# SynchDemod.net
KiCad netlist of a schematic drawn in Altium Designer
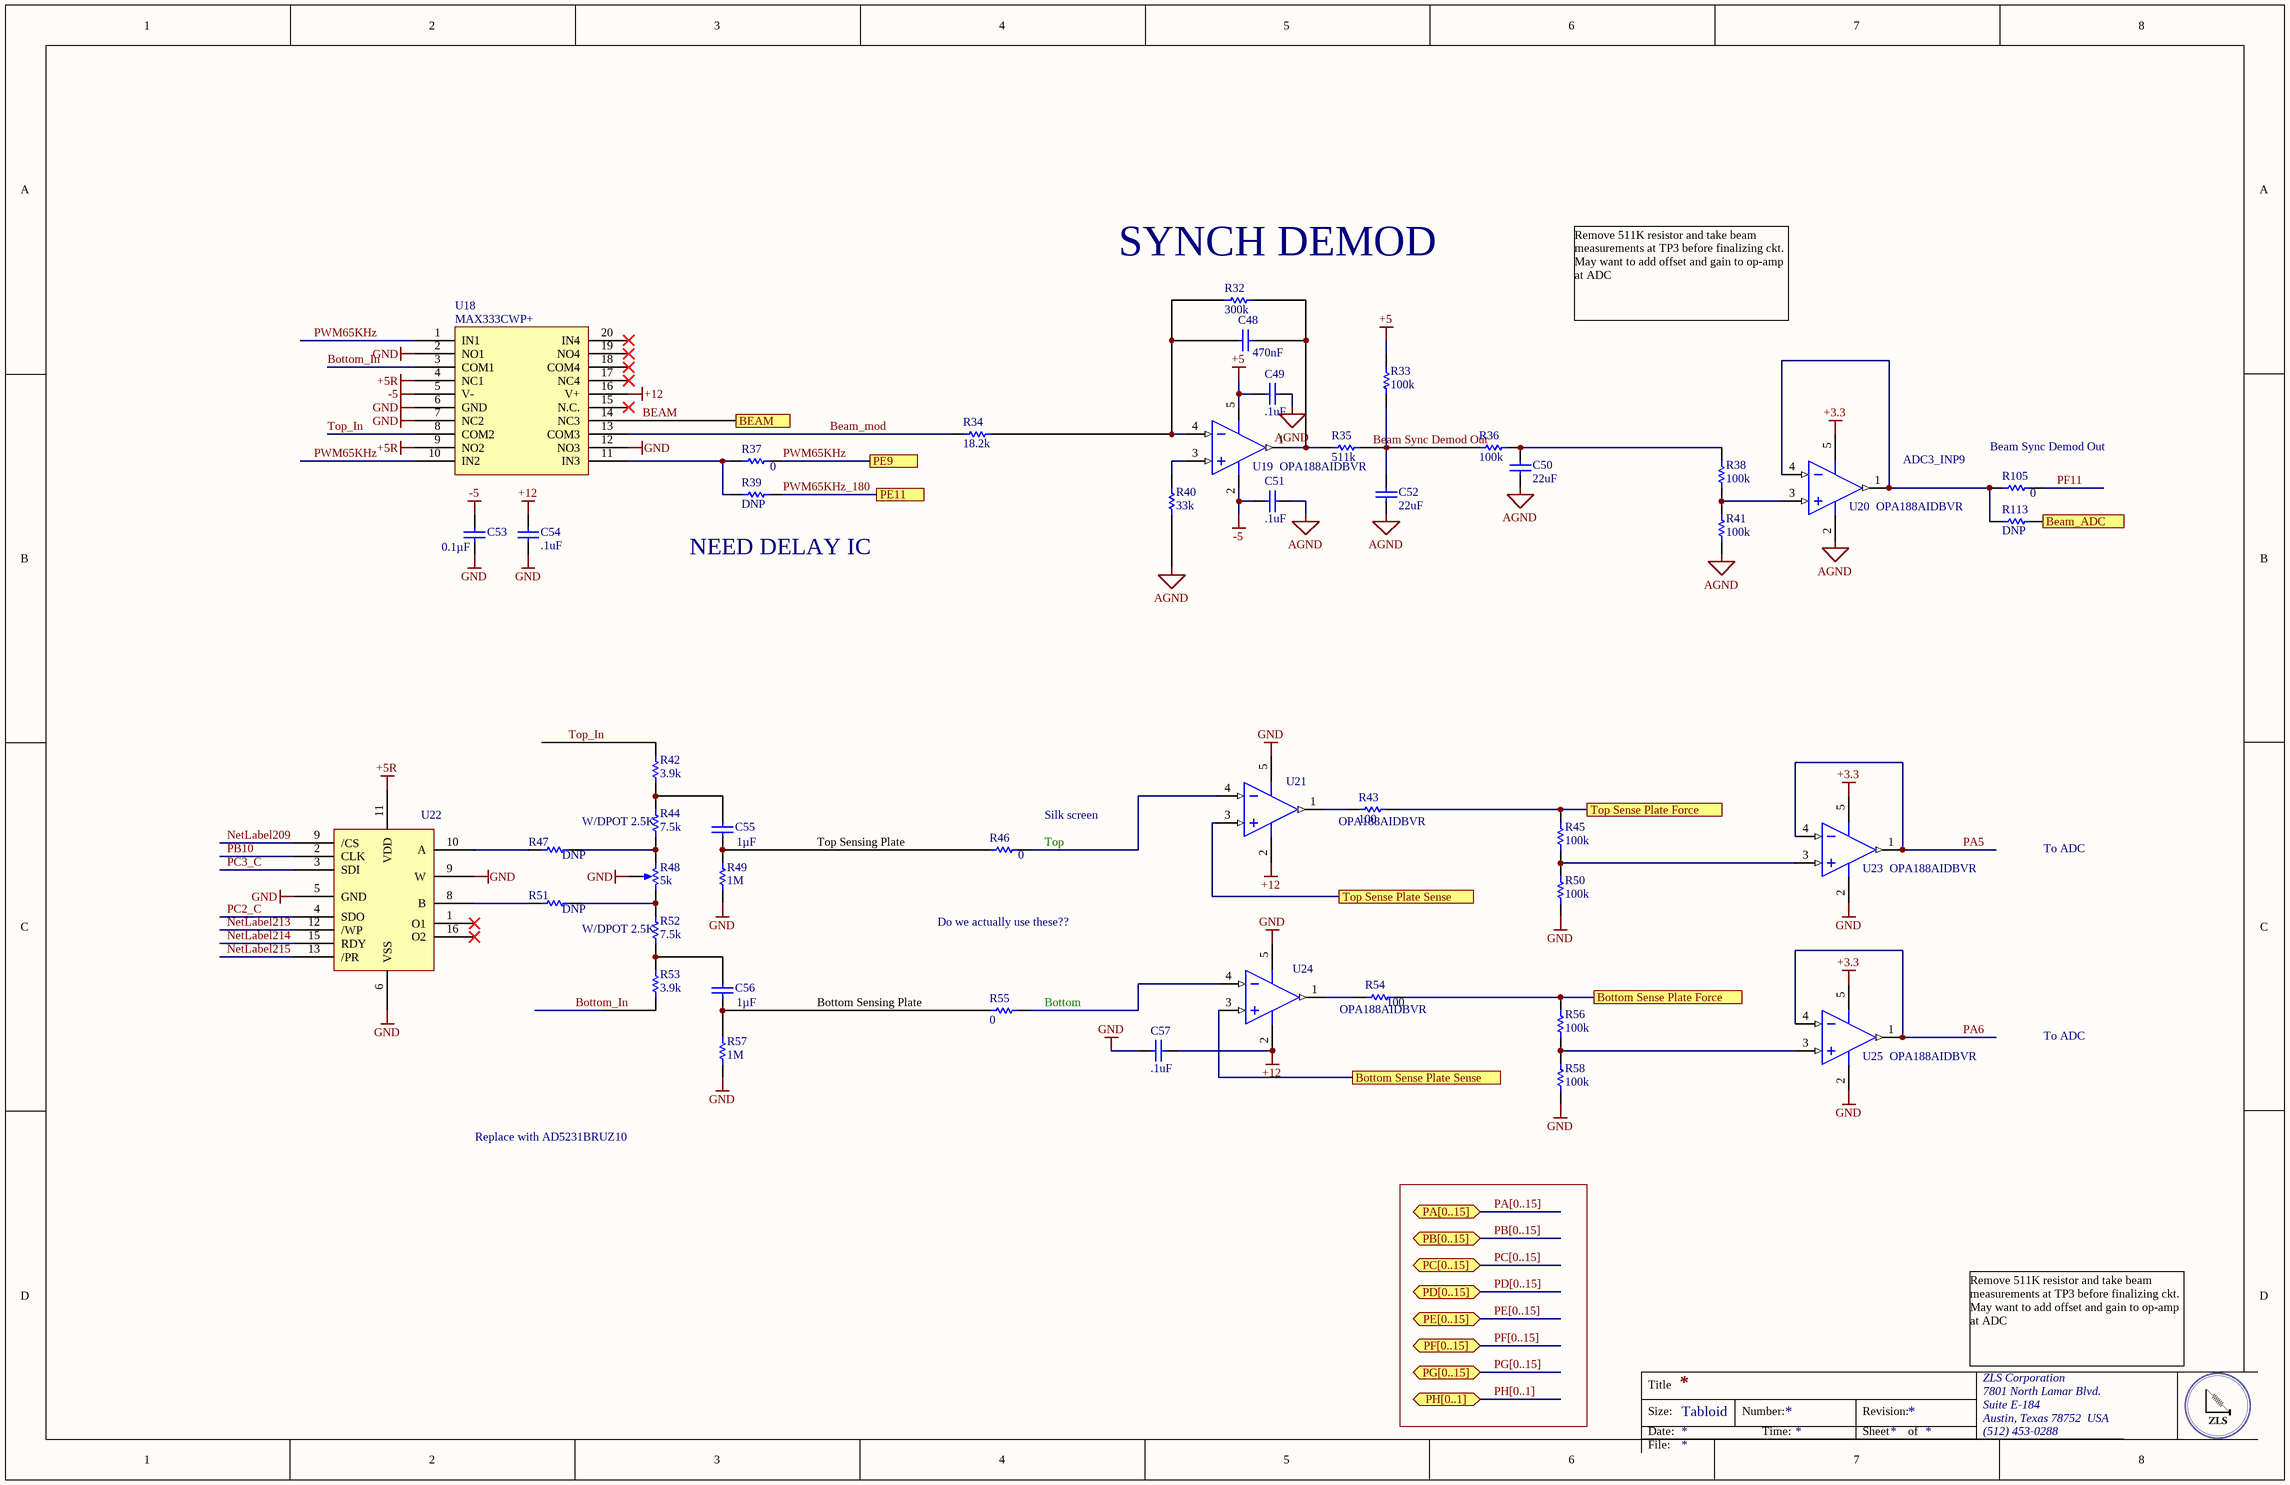
[diagram p0: SynchDemod.SchDoc]

(export (version "E")
  (design (tool "Eeschema 10.0.6"))
  (components
    (comp (ref "C48")
      (value "470nF")
      (footprint "CAPC0805(2012)75_L")
      (description "CAP 150pF 16V ±10% 0805 (2012 Metric) Thickness 0.75mm SMD")
      (fields (field (name "TOLERANCE") "Â±10%"))
      (libsource (lib "Altium Content Vault") (part "CMP-1036-02117-1"))
    )
    (comp (ref "C49")
      (value ".1uF")
      (footprint "CAPC0805(2012)75_L")
      (description "CAP 150pF 16V ±10% 0805 (2012 Metric) Thickness 0.75mm SMD")
      (fields (field (name "TOLERANCE") "Â±10%"))
      (libsource (lib "Altium Content Vault") (part "CMP-1036-02117-1"))
    )
    (comp (ref "C50")
      (value "22uF")
      (footprint "CAPC0805(2012)75_L")
      (description "CAP 150pF 16V ±10% 0805 (2012 Metric) Thickness 0.75mm SMD")
      (fields (field (name "TOLERANCE") "Â±10%"))
      (libsource (lib "Altium Content Vault") (part "CMP-1036-02117-1"))
    )
    (comp (ref "C51")
      (value ".1uF")
      (footprint "CAPC0805(2012)75_L")
      (description "CAP 150pF 16V ±10% 0805 (2012 Metric) Thickness 0.75mm SMD")
      (fields (field (name "TOLERANCE") "Â±10%"))
      (libsource (lib "Altium Content Vault") (part "CMP-1036-02117-1"))
    )
    (comp (ref "C52")
      (value "22uF")
      (footprint "CAPC0805(2012)75_L")
      (description "CAP 150pF 16V ±10% 0805 (2012 Metric) Thickness 0.75mm SMD")
      (fields (field (name "TOLERANCE") "Â±10%"))
      (libsource (lib "Altium Content Vault") (part "CMP-1036-02117-1"))
    )
    (comp (ref "C53")
      (value "CAP CER 0.1UF 25V X7R 0805")
      (footprint "CAPC0805(2012)145_N")
      (fields
        (field (name "MANUFACTURER") "Murata Electronics North America")
        (field (name "MANUFACTURER PART NUMBER") "GRM21BR71E104KA01L")
        (field (name "CAPACITANCE") "0.1µF")
        (field (name "TOLERANCE") "±10%")
      )
      (libsource (lib "Altium Content Vault") (part "CMP-1036-04795-1"))
    )
    (comp (ref "C54")
      (value ".1uF")
      (footprint "CAPC0805(2012)75_L")
      (description "CAP 150pF 16V ±10% 0805 (2012 Metric) Thickness 0.75mm SMD")
      (fields (field (name "TOLERANCE") "Â±10%"))
      (libsource (lib "Altium Content Vault") (part "CMP-1036-02117-1"))
    )
    (comp (ref "C55")
      (value "CAP CER 1UF 25V X7R 0805")
      (footprint "CAPC0805(2012)155_L")
      (fields
        (field (name "MANUFACTURER") "Murata Electronics North America")
        (field (name "MANUFACTURER PART NUMBER") "GRM21BR71E105KA99L")
        (field (name "CAPACITANCE") "1µF")
        (field (name "TOLERANCE") "±10%")
      )
      (libsource (lib "Altium Content Vault") (part "CMP-1036-04882-1"))
    )
    (comp (ref "C56")
      (value "CAP CER 1UF 25V X7R 0805")
      (footprint "CAPC0805(2012)155_L")
      (fields
        (field (name "MANUFACTURER") "Murata Electronics North America")
        (field (name "MANUFACTURER PART NUMBER") "GRM21BR71E105KA99L")
        (field (name "CAPACITANCE") "1µF")
        (field (name "TOLERANCE") "±10%")
      )
      (libsource (lib "Altium Content Vault") (part "CMP-1036-04882-1"))
    )
    (comp (ref "C57")
      (value ".1uF")
      (footprint "CAPC0805(2012)75_M")
      (description "CAP 33pF 25V ±2% 0805 (2012 Metric) Thickness 0.75mm SMD")
      (fields (field (name "TOLERANCE") "Â±2%"))
      (libsource (lib "Altium Content Vault") (part "CMP-1036-01414-1"))
    )
    (comp (ref "R32")
      (value "300k")
      (footprint "RESC0805(2012)_L")
      (description "2R55 0.125W 1% 0805 (2012 Metric)  SMD")
      (fields (field (name "TOLERANCE") "1 %") (field (name "POWER") "0.125 W"))
      (libsource (lib "Altium Content Vault") (part "CMP-1013-00215-1"))
    )
    (comp (ref "R33")
      (value "100k")
      (footprint "RESC0805(2012)_L")
      (description "2R55 0.125W 1% 0805 (2012 Metric)  SMD")
      (fields (field (name "TOLERANCE") "1 %") (field (name "POWER") "0.125 W"))
      (libsource (lib "Altium Content Vault") (part "CMP-1013-00215-1"))
    )
    (comp (ref "R34")
      (value "18.2k")
      (footprint "RESC0805(2012)_L")
      (description "2R55 0.125W 1% 0805 (2012 Metric)  SMD")
      (fields (field (name "TOLERANCE") "1 %") (field (name "POWER") "0.125 W"))
      (libsource (lib "Altium Content Vault") (part "CMP-1013-00215-1"))
    )
    (comp (ref "R35")
      (value "511k")
      (footprint "RESC0805(2012)_L")
      (description "2R55 0.125W 1% 0805 (2012 Metric)  SMD")
      (fields (field (name "TOLERANCE") "1 %") (field (name "POWER") "0.125 W"))
      (libsource (lib "Altium Content Vault") (part "CMP-1013-00215-1"))
    )
    (comp (ref "R36")
      (value "100k")
      (footprint "RESC0805(2012)_L")
      (description "2R55 0.125W 1% 0805 (2012 Metric)  SMD")
      (fields (field (name "TOLERANCE") "1 %") (field (name "POWER") "0.125 W"))
      (libsource (lib "Altium Content Vault") (part "CMP-1013-00215-1"))
    )
    (comp (ref "R37")
      (value "0")
      (footprint "RESC0805(2012)_L")
      (description "2R55 0.125W 1% 0805 (2012 Metric)  SMD")
      (fields (field (name "TOLERANCE") "1 %") (field (name "POWER") "0.125 W"))
      (libsource (lib "Altium Content Vault") (part "CMP-1013-00215-1"))
    )
    (comp (ref "R38")
      (value "100k")
      (footprint "RESC0805(2012)_L")
      (description "2R55 0.125W 1% 0805 (2012 Metric)  SMD")
      (fields (field (name "TOLERANCE") "1 %") (field (name "POWER") "0.125 W"))
      (libsource (lib "Altium Content Vault") (part "CMP-1013-00215-1"))
    )
    (comp (ref "R39")
      (value "DNP")
      (footprint "RESC0805(2012)_L")
      (description "2R55 0.125W 1% 0805 (2012 Metric)  SMD")
      (fields (field (name "TOLERANCE") "1 %") (field (name "POWER") "0.125 W"))
      (libsource (lib "Altium Content Vault") (part "CMP-1013-00215-1"))
    )
    (comp (ref "R40")
      (value "33k")
      (footprint "RESC0805(2012)_L")
      (description "2R55 0.125W 1% 0805 (2012 Metric)  SMD")
      (fields (field (name "TOLERANCE") "1 %") (field (name "POWER") "0.125 W"))
      (libsource (lib "Altium Content Vault") (part "CMP-1013-00215-1"))
    )
    (comp (ref "R41")
      (value "100k")
      (footprint "RESC0805(2012)_L")
      (description "2R55 0.125W 1% 0805 (2012 Metric)  SMD")
      (fields (field (name "TOLERANCE") "1 %") (field (name "POWER") "0.125 W"))
      (libsource (lib "Altium Content Vault") (part "CMP-1013-00215-1"))
    )
    (comp (ref "R42")
      (value "3.9k")
      (footprint "RESC0805(2012)_L")
      (description "2R55 0.125W 1% 0805 (2012 Metric)  SMD")
      (fields (field (name "TOLERANCE") "1 %") (field (name "POWER") "0.125 W"))
      (libsource (lib "Altium Content Vault") (part "CMP-1013-00215-1"))
    )
    (comp (ref "R43")
      (value "100")
      (footprint "RESC0805(2012)_L")
      (description "2R55 0.125W 1% 0805 (2012 Metric)  SMD")
      (fields (field (name "TOLERANCE") "1 %") (field (name "POWER") "0.125 W"))
      (libsource (lib "Altium Content Vault") (part "CMP-1013-00215-1"))
    )
    (comp (ref "R44")
      (value "7.5k")
      (footprint "RESC0805(2012)_L")
      (description "2R55 0.125W 1% 0805 (2012 Metric)  SMD")
      (fields (field (name "TOLERANCE") "1 %") (field (name "POWER") "0.125 W"))
      (libsource (lib "Altium Content Vault") (part "CMP-1013-00215-1"))
    )
    (comp (ref "R45")
      (value "100k")
      (footprint "RESC0805(2012)_L")
      (description "2R55 0.125W 1% 0805 (2012 Metric)  SMD")
      (fields (field (name "TOLERANCE") "1 %") (field (name "POWER") "0.125 W"))
      (libsource (lib "Altium Content Vault") (part "CMP-1013-00215-1"))
    )
    (comp (ref "R46")
      (value "0")
      (footprint "RESC0805(2012)_L")
      (description "2R55 0.125W 1% 0805 (2012 Metric)  SMD")
      (fields (field (name "TOLERANCE") "1 %") (field (name "POWER") "0.125 W"))
      (libsource (lib "Altium Content Vault") (part "CMP-1013-00215-1"))
    )
    (comp (ref "R47")
      (value "DNP")
      (footprint "RESC0805(2012)_L")
      (description "2R55 0.125W 1% 0805 (2012 Metric)  SMD")
      (fields (field (name "TOLERANCE") "1 %") (field (name "POWER") "0.125 W"))
      (libsource (lib "Altium Content Vault") (part "CMP-1013-00215-1"))
    )
    (comp (ref "R48")
      (value "TRIMMER 5K OHM 0.25W PC PIN")
      (footprint "Trimmer 2.54")
      (fields
        (field (name "MANUFACTURER") "Vishay Foil Resistors (Division of Vishay Precision Group)")
        (field (name "MANUFACTURER PART NUMBER") "Y00535K00000J0L")
        (field (name "RESISTANCE (OHMS)") "5k")
        (field (name "TOLERANCE") "±5%")
      )
      (libsource (lib "ZLS_Schematic_lib") (part "Trimmer"))
    )
    (comp (ref "R49")
      (value "1M")
      (footprint "RESC0805(2012)_L")
      (description "2R55 0.125W 1% 0805 (2012 Metric)  SMD")
      (fields (field (name "TOLERANCE") "1 %") (field (name "POWER") "0.125 W"))
      (libsource (lib "Altium Content Vault") (part "CMP-1013-00215-1"))
    )
    (comp (ref "R50")
      (value "100k")
      (footprint "RESC0805(2012)_L")
      (description "2R55 0.125W 1% 0805 (2012 Metric)  SMD")
      (fields (field (name "TOLERANCE") "1 %") (field (name "POWER") "0.125 W"))
      (libsource (lib "Altium Content Vault") (part "CMP-1013-00215-1"))
    )
    (comp (ref "R51")
      (value "DNP")
      (footprint "RESC0805(2012)_L")
      (description "2R55 0.125W 1% 0805 (2012 Metric)  SMD")
      (fields (field (name "TOLERANCE") "1 %") (field (name "POWER") "0.125 W"))
      (libsource (lib "Altium Content Vault") (part "CMP-1013-00215-1"))
    )
    (comp (ref "R52")
      (value "7.5k")
      (footprint "RESC0805(2012)_L")
      (description "2R55 0.125W 1% 0805 (2012 Metric)  SMD")
      (fields (field (name "TOLERANCE") "1 %") (field (name "POWER") "0.125 W"))
      (libsource (lib "Altium Content Vault") (part "CMP-1013-00215-1"))
    )
    (comp (ref "R53")
      (value "3.9k")
      (footprint "RESC0805(2012)_L")
      (description "2R55 0.125W 1% 0805 (2012 Metric)  SMD")
      (fields (field (name "TOLERANCE") "1 %") (field (name "POWER") "0.125 W"))
      (libsource (lib "Altium Content Vault") (part "CMP-1013-00215-1"))
    )
    (comp (ref "R54")
      (value "100")
      (footprint "RESC0805(2012)_L")
      (description "2R55 0.125W 1% 0805 (2012 Metric)  SMD")
      (fields (field (name "TOLERANCE") "1 %") (field (name "POWER") "0.125 W"))
      (libsource (lib "Altium Content Vault") (part "CMP-1013-00215-1"))
    )
    (comp (ref "R55")
      (value "0")
      (footprint "RESC0805(2012)_L")
      (description "2R55 0.125W 1% 0805 (2012 Metric)  SMD")
      (fields (field (name "TOLERANCE") "1 %") (field (name "POWER") "0.125 W"))
      (libsource (lib "Altium Content Vault") (part "CMP-1013-00215-1"))
    )
    (comp (ref "R56")
      (value "100k")
      (footprint "RESC0805(2012)_L")
      (description "2R55 0.125W 1% 0805 (2012 Metric)  SMD")
      (fields (field (name "TOLERANCE") "1 %") (field (name "POWER") "0.125 W"))
      (libsource (lib "Altium Content Vault") (part "CMP-1013-00215-1"))
    )
    (comp (ref "R57")
      (value "1M")
      (footprint "RESC0805(2012)_L")
      (description "2R55 0.125W 1% 0805 (2012 Metric)  SMD")
      (fields (field (name "TOLERANCE") "1 %") (field (name "POWER") "0.125 W"))
      (libsource (lib "Altium Content Vault") (part "CMP-1013-00215-1"))
    )
    (comp (ref "R58")
      (value "100k")
      (footprint "RESC0805(2012)_L")
      (description "2R55 0.125W 1% 0805 (2012 Metric)  SMD")
      (fields (field (name "TOLERANCE") "1 %") (field (name "POWER") "0.125 W"))
      (libsource (lib "Altium Content Vault") (part "CMP-1013-00215-1"))
    )
    (comp (ref "R105")
      (value "0")
      (footprint "RESC0805(2012)_L")
      (description "2R55 0.125W 1% 0805 (2012 Metric)  SMD")
      (fields (field (name "TOLERANCE") "1 %") (field (name "POWER") "0.125 W"))
      (libsource (lib "Altium Content Vault") (part "CMP-1013-00215-1"))
    )
    (comp (ref "R113")
      (value "DNP")
      (footprint "RESC0805(2012)_L")
      (description "2R55 0.125W 1% 0805 (2012 Metric)  SMD")
      (fields (field (name "TOLERANCE") "1 %") (field (name "POWER") "0.125 W"))
      (libsource (lib "Altium Content Vault") (part "CMP-1013-00215-1"))
    )
    (comp (ref "U18")
      (value "MAX333CWP+")
      (footprint "TSOP65P640X90-20N")
      (description "IC SWITCH QUAD SPDT 20TSSOP")
      (fields (field (name "MANUFACTURER") "Maxim") (field (name "MANUFACTURER PART NUMBER") "MAX333AEUP+"))
      (libsource (lib "ZLS_Schematic_lib") (part "MAX333CWP+"))
    )
    (comp (ref "U19")
      (value "OPA188AIDBVR")
      (footprint "DBV0005A_M")
      (fields (field (name "MANUFACTURER") "Texas Instruments"))
      (libsource (lib "Altium Content Vault") (part "CMP-0809-00005-2"))
    )
    (comp (ref "U20")
      (value "OPA188AIDBVR")
      (footprint "DBV0005A_M")
      (fields (field (name "MANUFACTURER") "Texas Instruments"))
      (libsource (lib "Altium Content Vault") (part "CMP-0809-00005-2"))
    )
    (comp (ref "U21")
      (value "OPA188AIDBVR")
      (footprint "DBV0005A_M")
      (fields (field (name "MANUFACTURER") "Texas Instruments"))
      (libsource (lib "Altium Content Vault") (part "CMP-0809-00005-2"))
    )
    (comp (ref "U22")
      (value "AD5231BRUZ10")
      (footprint "AD5231BRUZ10")
      (libsource (lib "ZLS_Schematic_lib") (part "AD5231BRUZ10"))
    )
    (comp (ref "U23")
      (value "OPA188AIDBVR")
      (footprint "DBV0005A_M")
      (fields (field (name "MANUFACTURER") "Texas Instruments"))
      (libsource (lib "Altium Content Vault") (part "CMP-0809-00005-2"))
    )
    (comp (ref "U24")
      (value "OPA188AIDBVR")
      (footprint "DBV0005A_M")
      (fields (field (name "MANUFACTURER") "Texas Instruments"))
      (libsource (lib "Altium Content Vault") (part "CMP-0809-00005-2"))
    )
    (comp (ref "U25")
      (value "OPA188AIDBVR")
      (footprint "DBV0005A_M")
      (fields (field (name "MANUFACTURER") "Texas Instruments"))
      (libsource (lib "Altium Content Vault") (part "CMP-0809-00005-2"))
    )
  )
  (nets
    (net (code "109") (name "+3.3") (class "Default")
      (node (ref "U20") (pin "5") (pinfunction "V+_5") (pintype "power_in"))
      (node (ref "U23") (pin "5") (pinfunction "V+_5") (pintype "power_in"))
      (node (ref "U25") (pin "5") (pinfunction "V+_5") (pintype "power_in"))
    )
    (net (code "110") (name "+5") (class "Default")
      (node (ref "C49") (pin "1") (pinfunction "1_1") (pintype "passive"))
      (node (ref "R33") (pin "2") (pinfunction "2_2") (pintype "passive"))
      (node (ref "U19") (pin "5") (pinfunction "V+_5") (pintype "power_in"))
    )
    (net (code "111") (name "+5R") (class "Default")
      (node (ref "U18") (pin "4") (pinfunction "NC1_4") (pintype "passive"))
      (node (ref "U18") (pin "9") (pinfunction "NO2_9") (pintype "passive"))
      (node (ref "U22") (pin "11") (pinfunction "VDD_11") (pintype "passive"))
    )
    (net (code "112") (name "+12") (class "Default")
      (node (ref "C54") (pin "2") (pinfunction "2_2") (pintype "passive"))
      (node (ref "C57") (pin "2") (pinfunction "2_2") (pintype "passive"))
      (node (ref "U18") (pin "16") (pinfunction "V+_16") (pintype "power_in"))
      (node (ref "U21") (pin "2") (pinfunction "V-_2") (pintype "power_in"))
      (node (ref "U24") (pin "2") (pinfunction "V-_2") (pintype "power_in"))
    )
    (net (code "113") (name "-5") (class "Default")
      (node (ref "C51") (pin "1") (pinfunction "1_1") (pintype "passive"))
      (node (ref "C53") (pin "1") (pinfunction "1_1") (pintype "passive"))
      (node (ref "U18") (pin "5") (pinfunction "V-_5") (pintype "power_in"))
      (node (ref "U19") (pin "2") (pinfunction "V-_2") (pintype "power_in"))
    )
    (net (code "114") (name "/BEAM") (class "Default")
      (node (ref "U18") (pin "14") (pinfunction "NC3_14") (pintype "passive"))
    )
    (net (code "115") (name "/Beam Sync Demod Out") (class "Default")
      (node (ref "C52") (pin "2") (pinfunction "2_2") (pintype "passive"))
      (node (ref "R33") (pin "1") (pinfunction "1_1") (pintype "passive"))
      (node (ref "R35") (pin "1") (pinfunction "1_1") (pintype "passive"))
      (node (ref "R36") (pin "2") (pinfunction "2_2") (pintype "passive"))
    )
    (net (code "116") (name "/Beam_ADC") (class "Default")
      (node (ref "R113") (pin "1") (pinfunction "1_1") (pintype "passive"))
    )
    (net (code "117") (name "/Beam_mod") (class "Default")
      (node (ref "R34") (pin "2") (pinfunction "2_2") (pintype "passive"))
      (node (ref "U18") (pin "13") (pinfunction "COM3_13") (pintype "passive"))
    )
    (net (code "118") (name "/Bottom Sense Plate Force") (class "Default")
      (node (ref "R54") (pin "1") (pinfunction "1_1") (pintype "passive"))
      (node (ref "R56") (pin "2") (pinfunction "2_2") (pintype "passive"))
    )
    (net (code "119") (name "/Bottom Sense Plate Sense") (class "Default")
      (node (ref "U24") (pin "3") (pinfunction "IN+_3") (pintype "input"))
    )
    (net (code "120") (name "/Bottom_In") (class "Default")
      (node (ref "R53") (pin "1") (pinfunction "1_1") (pintype "passive"))
      (node (ref "U18") (pin "3") (pinfunction "COM1_3") (pintype "passive"))
    )
    (net (code "121") (name "/NetLabel209") (class "Default")
      (node (ref "U22") (pin "9") (pinfunction "/CS_9") (pintype "passive"))
    )
    (net (code "122") (name "/NetLabel213") (class "Default")
      (node (ref "U22") (pin "12") (pinfunction "/WP_12") (pintype "passive"))
    )
    (net (code "123") (name "/NetLabel214") (class "Default")
      (node (ref "U22") (pin "15") (pinfunction "RDY_15") (pintype "passive"))
    )
    (net (code "124") (name "/NetLabel215") (class "Default")
      (node (ref "U22") (pin "13") (pinfunction "/PR_13") (pintype "passive"))
    )
    (net (code "125") (name "/PA5") (class "Default")
      (node (ref "U23") (pin "1") (pinfunction "OUT_1") (pintype "output"))
      (node (ref "U23") (pin "4") (pinfunction "IN-_4") (pintype "input"))
    )
    (net (code "126") (name "/PA6") (class "Default")
      (node (ref "U25") (pin "1") (pinfunction "OUT_1") (pintype "output"))
      (node (ref "U25") (pin "4") (pinfunction "IN-_4") (pintype "input"))
    )
    (net (code "128") (name "/PB10") (class "Default")
      (node (ref "U22") (pin "2") (pinfunction "CLK_2") (pintype "passive"))
    )
    (net (code "130") (name "/PC2_C") (class "Default")
      (node (ref "U22") (pin "4") (pinfunction "SDO_4") (pintype "passive"))
    )
    (net (code "131") (name "/PC3_C") (class "Default")
      (node (ref "U22") (pin "3") (pinfunction "SDI_3") (pintype "passive"))
    )
    (net (code "134") (name "/PE9") (class "Default")
      (node (ref "R37") (pin "1") (pinfunction "1_1") (pintype "passive"))
      (node (ref "U18") (pin "1") (pinfunction "IN1_1") (pintype "passive"))
      (node (ref "U18") (pin "10") (pinfunction "IN2_10") (pintype "passive"))
    )
    (net (code "135") (name "/PE11") (class "Default")
      (node (ref "R39") (pin "1") (pinfunction "1_1") (pintype "passive"))
    )
    (net (code "137") (name "/PF11") (class "Default")
      (node (ref "R105") (pin "1") (pinfunction "1_1") (pintype "passive"))
    )
    (net (code "141") (name "/Top Sense Plate Force") (class "Default")
      (node (ref "R43") (pin "1") (pinfunction "1_1") (pintype "passive"))
      (node (ref "R45") (pin "2") (pinfunction "2_2") (pintype "passive"))
    )
    (net (code "142") (name "/Top Sense Plate Sense") (class "Default")
      (node (ref "U21") (pin "3") (pinfunction "IN+_3") (pintype "input"))
    )
    (net (code "143") (name "/Top_In") (class "Default")
      (node (ref "R42") (pin "2") (pinfunction "2_2") (pintype "passive"))
      (node (ref "U18") (pin "8") (pinfunction "COM2_8") (pintype "passive"))
    )
    (net (code "144") (name "AGND") (class "Default")
      (node (ref "C49") (pin "2") (pinfunction "2_2") (pintype "passive"))
      (node (ref "C50") (pin "1") (pinfunction "1_1") (pintype "passive"))
      (node (ref "C51") (pin "2") (pinfunction "2_2") (pintype "passive"))
      (node (ref "C52") (pin "1") (pinfunction "1_1") (pintype "passive"))
      (node (ref "R40") (pin "1") (pinfunction "1_1") (pintype "passive"))
      (node (ref "R41") (pin "1") (pinfunction "1_1") (pintype "passive"))
      (node (ref "U20") (pin "2") (pinfunction "V-_2") (pintype "power_in"))
    )
    (net (code "145") (name "GND") (class "Default")
      (node (ref "C53") (pin "2") (pinfunction "2_2") (pintype "passive"))
      (node (ref "C54") (pin "1") (pinfunction "1_1") (pintype "passive"))
      (node (ref "C57") (pin "1") (pinfunction "1_1") (pintype "passive"))
      (node (ref "R48") (pin "2") (pinfunction "b_2") (pintype "passive"))
      (node (ref "R49") (pin "1") (pinfunction "1_1") (pintype "passive"))
      (node (ref "R50") (pin "1") (pinfunction "1_1") (pintype "passive"))
      (node (ref "R57") (pin "1") (pinfunction "1_1") (pintype "passive"))
      (node (ref "R58") (pin "1") (pinfunction "1_1") (pintype "passive"))
      (node (ref "U18") (pin "12") (pinfunction "NO3_12") (pintype "passive"))
      (node (ref "U18") (pin "2") (pinfunction "NO1_2") (pintype "passive"))
      (node (ref "U18") (pin "6") (pinfunction "GND_6") (pintype "passive"))
      (node (ref "U18") (pin "7") (pinfunction "NC2_7") (pintype "passive"))
      (node (ref "U21") (pin "5") (pinfunction "V+_5") (pintype "power_in"))
      (node (ref "U22") (pin "5") (pinfunction "GND_5") (pintype "passive"))
      (node (ref "U22") (pin "6") (pinfunction "VSS_6") (pintype "passive"))
      (node (ref "U22") (pin "9") (pinfunction "W_9") (pintype "passive"))
      (node (ref "U23") (pin "2") (pinfunction "V-_2") (pintype "power_in"))
      (node (ref "U24") (pin "5") (pinfunction "V+_5") (pintype "power_in"))
      (node (ref "U25") (pin "2") (pinfunction "V-_2") (pintype "power_in"))
    )
    (net (code "146") (name "Net-(C50-Pad2)") (class "Default")
      (node (ref "C50") (pin "2") (pinfunction "2_2") (pintype "passive"))
      (node (ref "R36") (pin "1") (pinfunction "1_1") (pintype "passive"))
      (node (ref "R38") (pin "2") (pinfunction "2_2") (pintype "passive"))
    )
    (net (code "147") (name "Net-(C55-Pad1)") (class "Default")
      (node (ref "C55") (pin "1") (pinfunction "1_1") (pintype "passive"))
      (node (ref "R46") (pin "2") (pinfunction "2_2") (pintype "passive"))
      (node (ref "R49") (pin "2") (pinfunction "2_2") (pintype "passive"))
    )
    (net (code "148") (name "Net-(C55-Pad2)") (class "Default")
      (node (ref "C55") (pin "2") (pinfunction "2_2") (pintype "passive"))
      (node (ref "R42") (pin "1") (pinfunction "1_1") (pintype "passive"))
      (node (ref "R44") (pin "2") (pinfunction "2_2") (pintype "passive"))
    )
    (net (code "149") (name "Net-(C56-Pad1)") (class "Default")
      (node (ref "C56") (pin "1") (pinfunction "1_1") (pintype "passive"))
      (node (ref "R55") (pin "2") (pinfunction "2_2") (pintype "passive"))
      (node (ref "R57") (pin "2") (pinfunction "2_2") (pintype "passive"))
    )
    (net (code "150") (name "Net-(C56-Pad2)") (class "Default")
      (node (ref "C56") (pin "2") (pinfunction "2_2") (pintype "passive"))
      (node (ref "R52") (pin "1") (pinfunction "1_1") (pintype "passive"))
      (node (ref "R53") (pin "2") (pinfunction "2_2") (pintype "passive"))
    )
    (net (code "151") (name "Net-(R48-a)") (class "Default")
      (node (ref "R44") (pin "1") (pinfunction "1_1") (pintype "passive"))
      (node (ref "R47") (pin "1") (pinfunction "1_1") (pintype "passive"))
      (node (ref "R48") (pin "1") (pinfunction "a_1") (pintype "passive"))
    )
    (net (code "152") (name "Net-(R48-c)") (class "Default")
      (node (ref "R48") (pin "3") (pinfunction "c_3") (pintype "passive"))
      (node (ref "R51") (pin "1") (pinfunction "1_1") (pintype "passive"))
      (node (ref "R52") (pin "2") (pinfunction "2_2") (pintype "passive"))
    )
    (net (code "153") (name "Net-(U18-IN3)") (class "Default")
      (node (ref "R37") (pin "2") (pinfunction "2_2") (pintype "passive"))
      (node (ref "R39") (pin "2") (pinfunction "2_2") (pintype "passive"))
      (node (ref "U18") (pin "11") (pinfunction "IN3_11") (pintype "passive"))
    )
    (net (code "154") (name "Net-(U19-IN+)") (class "Default")
      (node (ref "R40") (pin "2") (pinfunction "2_2") (pintype "passive"))
      (node (ref "U19") (pin "3") (pinfunction "IN+_3") (pintype "input"))
    )
    (net (code "155") (name "Net-(U19-IN-)") (class "Default")
      (node (ref "C48") (pin "1") (pinfunction "1_1") (pintype "passive"))
      (node (ref "R32") (pin "2") (pinfunction "2_2") (pintype "passive"))
      (node (ref "R34") (pin "1") (pinfunction "1_1") (pintype "passive"))
      (node (ref "U19") (pin "4") (pinfunction "IN-_4") (pintype "input"))
    )
    (net (code "156") (name "Net-(U19-OUT)") (class "Default")
      (node (ref "C48") (pin "2") (pinfunction "2_2") (pintype "passive"))
      (node (ref "R32") (pin "1") (pinfunction "1_1") (pintype "passive"))
      (node (ref "R35") (pin "2") (pinfunction "2_2") (pintype "passive"))
      (node (ref "U19") (pin "1") (pinfunction "OUT_1") (pintype "output"))
    )
    (net (code "157") (name "Net-(U20-IN+)") (class "Default")
      (node (ref "R38") (pin "1") (pinfunction "1_1") (pintype "passive"))
      (node (ref "R41") (pin "2") (pinfunction "2_2") (pintype "passive"))
      (node (ref "U20") (pin "3") (pinfunction "IN+_3") (pintype "input"))
    )
    (net (code "158") (name "Net-(U20-IN-)") (class "Default")
      (node (ref "R105") (pin "2") (pinfunction "2_2") (pintype "passive"))
      (node (ref "R113") (pin "2") (pinfunction "2_2") (pintype "passive"))
      (node (ref "U20") (pin "1") (pinfunction "OUT_1") (pintype "output"))
      (node (ref "U20") (pin "4") (pinfunction "IN-_4") (pintype "input"))
    )
    (net (code "159") (name "Net-(U21-IN-)") (class "Default")
      (node (ref "R46") (pin "1") (pinfunction "1_1") (pintype "passive"))
      (node (ref "U21") (pin "4") (pinfunction "IN-_4") (pintype "input"))
    )
    (net (code "160") (name "Net-(U21-OUT)") (class "Default")
      (node (ref "R43") (pin "2") (pinfunction "2_2") (pintype "passive"))
      (node (ref "U21") (pin "1") (pinfunction "OUT_1") (pintype "output"))
    )
    (net (code "161") (name "Net-(U22-A)") (class "Default")
      (node (ref "R47") (pin "2") (pinfunction "2_2") (pintype "passive"))
      (node (ref "U22") (pin "10") (pinfunction "A_10") (pintype "passive"))
    )
    (net (code "162") (name "Net-(U22-B)") (class "Default")
      (node (ref "R51") (pin "2") (pinfunction "2_2") (pintype "passive"))
      (node (ref "U22") (pin "8") (pinfunction "B_8") (pintype "passive"))
    )
    (net (code "163") (name "Net-(U23-IN+)") (class "Default")
      (node (ref "R45") (pin "1") (pinfunction "1_1") (pintype "passive"))
      (node (ref "R50") (pin "2") (pinfunction "2_2") (pintype "passive"))
      (node (ref "U23") (pin "3") (pinfunction "IN+_3") (pintype "input"))
    )
    (net (code "164") (name "Net-(U24-IN-)") (class "Default")
      (node (ref "R55") (pin "1") (pinfunction "1_1") (pintype "passive"))
      (node (ref "U24") (pin "4") (pinfunction "IN-_4") (pintype "input"))
    )
    (net (code "165") (name "Net-(U24-OUT)") (class "Default")
      (node (ref "R54") (pin "2") (pinfunction "2_2") (pintype "passive"))
      (node (ref "U24") (pin "1") (pinfunction "OUT_1") (pintype "output"))
    )
    (net (code "166") (name "Net-(U25-IN+)") (class "Default")
      (node (ref "R56") (pin "1") (pinfunction "1_1") (pintype "passive"))
      (node (ref "R58") (pin "2") (pinfunction "2_2") (pintype "passive"))
      (node (ref "U25") (pin "3") (pinfunction "IN+_3") (pintype "input"))
    )
    (net (code "167") (name "unconnected-(U18-COM4-Pad18)") (class "Default")
      (node (ref "U18") (pin "18") (pinfunction "COM4_18") (pintype "passive+no_connect"))
    )
    (net (code "168") (name "unconnected-(U18-IN4-Pad20)") (class "Default")
      (node (ref "U18") (pin "20") (pinfunction "IN4_20") (pintype "passive+no_connect"))
    )
    (net (code "169") (name "unconnected-(U18-N.C.-Pad15)") (class "Default")
      (node (ref "U18") (pin "15") (pinfunction "N.C._15") (pintype "passive+no_connect"))
    )
    (net (code "170") (name "unconnected-(U18-NC4-Pad17)") (class "Default")
      (node (ref "U18") (pin "17") (pinfunction "NC4_17") (pintype "passive+no_connect"))
    )
    (net (code "171") (name "unconnected-(U18-NO4-Pad19)") (class "Default")
      (node (ref "U18") (pin "19") (pinfunction "NO4_19") (pintype "passive+no_connect"))
    )
    (net (code "172") (name "unconnected-(U22-O1-Pad1)") (class "Default")
      (node (ref "U22") (pin "1") (pinfunction "O1_1") (pintype "passive+no_connect"))
    )
    (net (code "173") (name "unconnected-(U22-O2-Pad16)") (class "Default")
      (node (ref "U22") (pin "16") (pinfunction "O2_16") (pintype "passive+no_connect"))
    )
  )
)
